# LoRaWAN.net
KiCad netlist of a schematic drawn in Altium Designer
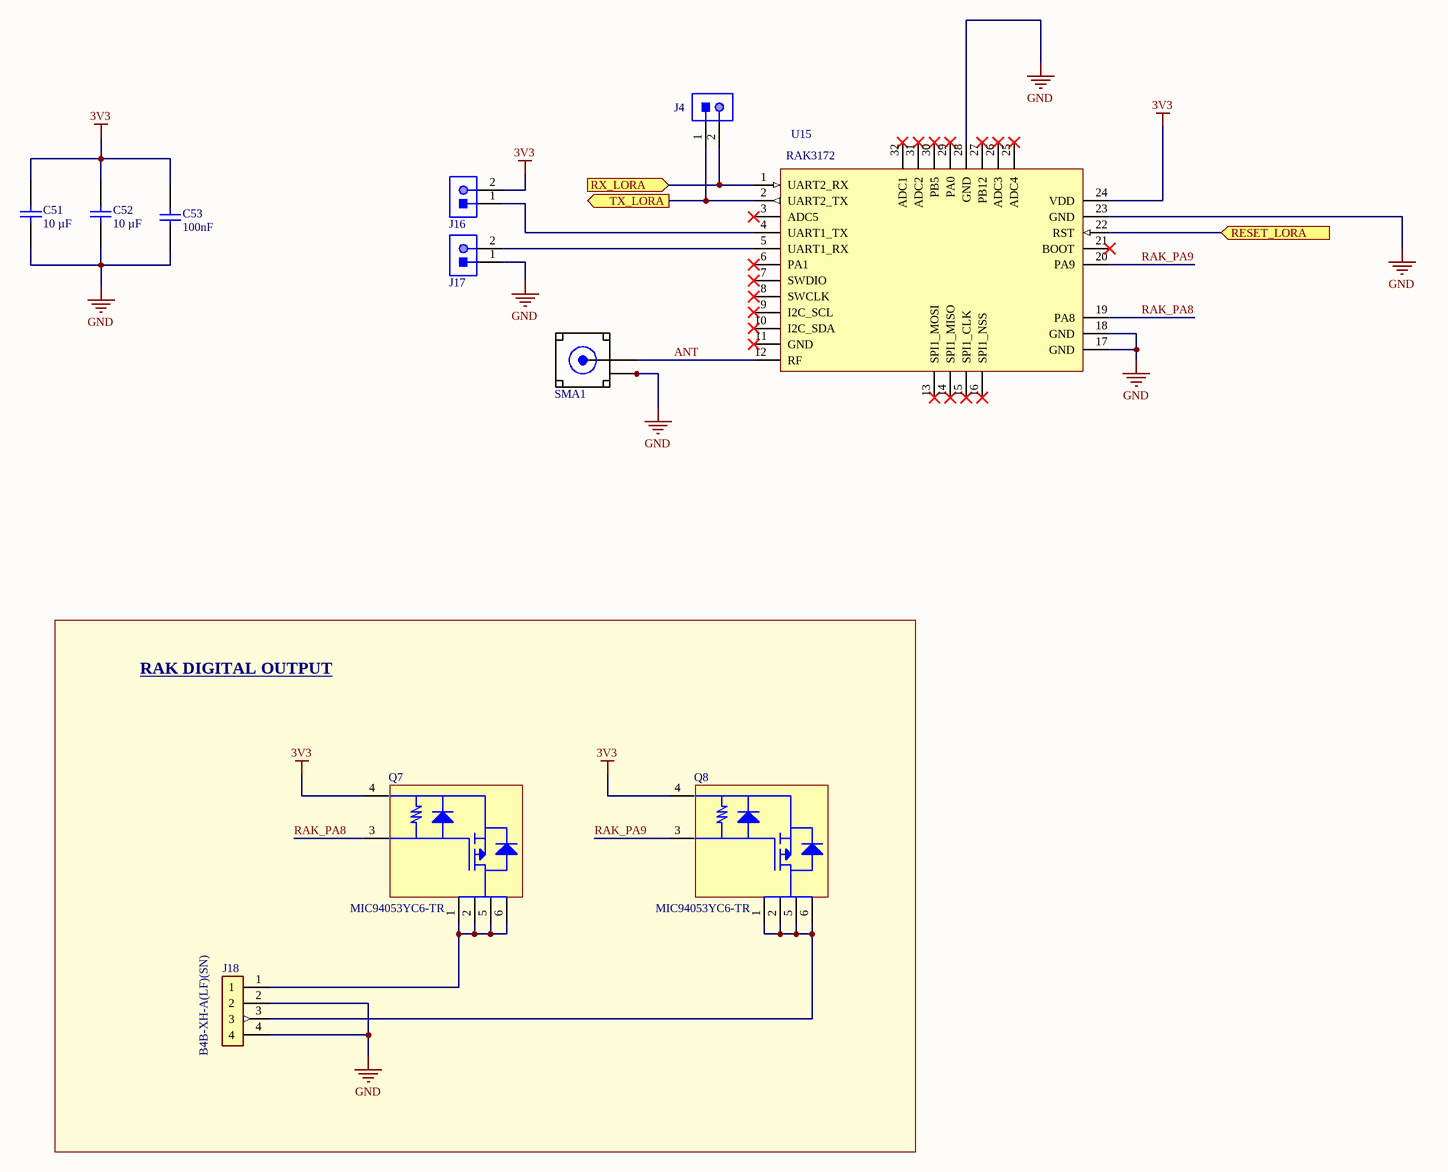
[diagram p0: LoRaWAN.SchDoc]

(export (version "E")
  (design (tool "Eeschema 10.0.6"))
  (components
    (comp (ref "C51")
      (value "10 µF")
      (footprint "Cap 0805 (2012 Metric)")
      (description "10 µF ±10% 10V Ceramic Capacitor X5R 0805 (2012 Metric)")
      (fields
        (field (name "MANUFACTURER") "Cal-Chip Electronics")
        (field (name "MANUFACTURER PART NUMBER") "GMC21X5R106K10NT")
      )
      (libsource (lib "Daniel_Integrated_Library") (part "Capacitor"))
    )
    (comp (ref "C52")
      (value "10 µF")
      (footprint "Cap 0805 (2012 Metric)")
      (description "10 µF ±10% 10V Ceramic Capacitor X5R 0805 (2012 Metric)")
      (fields
        (field (name "MANUFACTURER") "Cal-Chip Electronics")
        (field (name "MANUFACTURER PART NUMBER") "GMC21X5R106K10NT")
      )
      (libsource (lib "Daniel_Integrated_Library") (part "Capacitor"))
    )
    (comp (ref "C53")
      (value "100nF")
      (footprint "Cap 0805 (2012 Metric)")
      (description "Cap Ceramic 0.1uF 50V X7R 10% Pad SMD 0805 125C Automotive T/R")
      (fields
        (field (name "MANUFACTURER") "Samsung")
        (field (name "MANUFACTURER PART NUMBER") "CL21B104KBC5PNL")
      )
      (libsource (lib "Daniel_Integrated_Library") (part "Capacitor"))
    )
    (comp (ref "J4")
      (value "Header 2x1")
      (footprint "Header 2x1")
      (libsource (lib "Daniel_Integrated_Library") (part "Header 2x1"))
    )
    (comp (ref "J16")
      (value "Header 2x1")
      (footprint "Header 2x1")
      (libsource (lib "") (part "Header 2x1_1"))
    )
    (comp (ref "J17")
      (value "Header 2x1")
      (footprint "Header 2x1")
      (libsource (lib "") (part "Header 2x1_1"))
    )
    (comp (ref "J18")
      (value "B4B-XH-A(LF)(SN)")
      (footprint "B4B-XH-A(LF)(SN)")
      (fields (field (name "MANUFACTURER") "JST"))
      (libsource (lib "stratos") (part "B4B-XH-A(LF)(SN)"))
    )
    (comp (ref "Q7")
      (value "MIC94053YC6-TR")
      (footprint "SC-70-6")
      (description "P-Channel 6V 2A (Ta) 270mW (Ta) Surface Mount SC-70-6")
      (fields (field (name "MANUFACTURER") "Microchip"))
      (libsource (lib "Daniel_Integrated_Library") (part "TransistorMosfet(Load)"))
    )
    (comp (ref "Q8")
      (value "MIC94053YC6-TR")
      (footprint "SC-70-6")
      (description "P-Channel 6V 2A (Ta) 270mW (Ta) Surface Mount SC-70-6")
      (fields (field (name "MANUFACTURER") "Microchip"))
      (libsource (lib "Daniel_Integrated_Library") (part "TransistorMosfet(Load)"))
    )
    (comp (ref "SMA1")
      (value "https://www.digikey.com/products/en?keywords=5-1814400-1")
      (footprint "5-1814400-1+ant")
      (description "CONN SMA JACK R/A 50 OHM PCB")
      (fields
        (field (name "MANUFACTURER") "AMP - TE CONNECTIVITY")
        (field (name "MANUFACTURER PART NUMBER") "5-1814400-1")
      )
      (libsource (lib "MyLib") (part "5-1814400-1"))
    )
    (comp (ref "U15")
      (value "RAK3172")
      (footprint "RAK3172")
      (description "RAK3172 WisDuo LPWAN Module")
      (fields (field (name "MANUFACTURER") "RAK"))
      (libsource (lib "stratos") (part "RAK3172"))
    )
  )
  (nets
    (net (code "2") (name "/ANT") (class "Default")
      (node (ref "SMA1") (pin "5") (pinfunction "SIGNAL_5") (pintype "passive"))
      (node (ref "U15") (pin "12") (pinfunction "RF_12") (pintype "passive"))
    )
    (net (code "3") (name "/RAK_PA8") (class "Default")
      (node (ref "Q7") (pin "3") (pinfunction "G_3") (pintype "passive"))
      (node (ref "U15") (pin "19") (pinfunction "PA8_19") (pintype "passive"))
    )
    (net (code "4") (name "/RAK_PA9") (class "Default")
      (node (ref "Q8") (pin "3") (pinfunction "G_3") (pintype "passive"))
      (node (ref "U15") (pin "20") (pinfunction "PA9_20") (pintype "passive"))
    )
    (net (code "5") (name "/RESET_LORA") (class "Default")
      (node (ref "U15") (pin "22") (pinfunction "RST_22") (pintype "input"))
    )
    (net (code "6") (name "/RX_LORA") (class "Default")
      (node (ref "J4") (pin "2") (pinfunction "2_2") (pintype "passive"))
      (node (ref "U15") (pin "1") (pinfunction "UART2_RX_1") (pintype "input"))
    )
    (net (code "7") (name "/TX_LORA") (class "Default")
      (node (ref "J4") (pin "1") (pinfunction "1_1") (pintype "passive"))
      (node (ref "U15") (pin "2") (pinfunction "UART2_TX_2") (pintype "output"))
    )
    (net (code "8") (name "3V3") (class "Default")
      (node (ref "C51") (pin "1") (pinfunction "1_1") (pintype "passive"))
      (node (ref "C52") (pin "1") (pinfunction "1_1") (pintype "passive"))
      (node (ref "C53") (pin "1") (pinfunction "1_1") (pintype "passive"))
      (node (ref "J16") (pin "2") (pinfunction "2_2") (pintype "passive"))
      (node (ref "Q7") (pin "4") (pinfunction "S_4") (pintype "passive"))
      (node (ref "Q8") (pin "4") (pinfunction "S_4") (pintype "passive"))
      (node (ref "U15") (pin "24") (pinfunction "VDD_24") (pintype "passive"))
    )
    (net (code "9") (name "GND") (class "Default")
      (node (ref "C51") (pin "2") (pinfunction "2_2") (pintype "passive"))
      (node (ref "C52") (pin "2") (pinfunction "2_2") (pintype "passive"))
      (node (ref "C53") (pin "2") (pinfunction "2_2") (pintype "passive"))
      (node (ref "J17") (pin "1") (pinfunction "1_1") (pintype "passive"))
      (node (ref "J18") (pin "2") (pinfunction "2_2") (pintype "passive"))
      (node (ref "J18") (pin "4") (pinfunction "4_4") (pintype "passive"))
      (node (ref "SMA1") (pin "1") (pinfunction "GND_1") (pintype "power_in"))
      (node (ref "SMA1") (pin "2") (pinfunction "GND_2") (pintype "power_in"))
      (node (ref "SMA1") (pin "3") (pinfunction "GND_3") (pintype "power_in"))
      (node (ref "SMA1") (pin "4") (pinfunction "GND_4") (pintype "power_in"))
      (node (ref "U15") (pin "17") (pinfunction "GND_17") (pintype "passive"))
      (node (ref "U15") (pin "18") (pinfunction "GND_18") (pintype "passive"))
      (node (ref "U15") (pin "23") (pinfunction "GND_23") (pintype "passive"))
      (node (ref "U15") (pin "28") (pinfunction "GND_28") (pintype "passive"))
    )
    (net (code "10") (name "Net-(J18-Pad1)") (class "Default")
      (node (ref "J18") (pin "1") (pinfunction "1_1") (pintype "passive"))
      (node (ref "Q7") (pin "1") (pinfunction "D_1") (pintype "passive"))
      (node (ref "Q7") (pin "2") (pinfunction "D_2") (pintype "passive"))
      (node (ref "Q7") (pin "5") (pinfunction "D_5") (pintype "passive"))
      (node (ref "Q7") (pin "6") (pinfunction "D_6") (pintype "passive"))
    )
    (net (code "11") (name "Net-(J18-Pad3)") (class "Default")
      (node (ref "J18") (pin "3") (pinfunction "3_3") (pintype "output"))
      (node (ref "Q8") (pin "1") (pinfunction "D_1") (pintype "passive"))
      (node (ref "Q8") (pin "2") (pinfunction "D_2") (pintype "passive"))
      (node (ref "Q8") (pin "5") (pinfunction "D_5") (pintype "passive"))
      (node (ref "Q8") (pin "6") (pinfunction "D_6") (pintype "passive"))
    )
    (net (code "12") (name "Net-(U15-UART1_RX)") (class "Default")
      (node (ref "J17") (pin "2") (pinfunction "2_2") (pintype "passive"))
      (node (ref "U15") (pin "5") (pinfunction "UART1_RX_5") (pintype "passive"))
    )
    (net (code "13") (name "Net-(U15-UART1_TX)") (class "Default")
      (node (ref "J16") (pin "1") (pinfunction "1_1") (pintype "passive"))
      (node (ref "U15") (pin "4") (pinfunction "UART1_TX_4") (pintype "passive"))
    )
    (net (code "14") (name "unconnected-(U15-ADC1-Pad32)") (class "Default")
      (node (ref "U15") (pin "32") (pinfunction "ADC1_32") (pintype "passive+no_connect"))
    )
    (net (code "15") (name "unconnected-(U15-ADC2-Pad31)") (class "Default")
      (node (ref "U15") (pin "31") (pinfunction "ADC2_31") (pintype "passive+no_connect"))
    )
    (net (code "16") (name "unconnected-(U15-ADC3-Pad26)") (class "Default")
      (node (ref "U15") (pin "26") (pinfunction "ADC3_26") (pintype "passive+no_connect"))
    )
    (net (code "17") (name "unconnected-(U15-ADC4-Pad25)") (class "Default")
      (node (ref "U15") (pin "25") (pinfunction "ADC4_25") (pintype "passive+no_connect"))
    )
    (net (code "18") (name "unconnected-(U15-ADC5-Pad3)") (class "Default")
      (node (ref "U15") (pin "3") (pinfunction "ADC5_3") (pintype "passive+no_connect"))
    )
    (net (code "19") (name "unconnected-(U15-BOOT-Pad21)") (class "Default")
      (node (ref "U15") (pin "21") (pinfunction "BOOT_21") (pintype "passive+no_connect"))
    )
    (net (code "20") (name "unconnected-(U15-GND-Pad11)") (class "Default")
      (node (ref "U15") (pin "11") (pinfunction "GND_11") (pintype "passive+no_connect"))
    )
    (net (code "21") (name "unconnected-(U15-I2C_SCL-Pad9)") (class "Default")
      (node (ref "U15") (pin "9") (pinfunction "I2C_SCL_9") (pintype "passive+no_connect"))
    )
    (net (code "22") (name "unconnected-(U15-I2C_SDA-Pad10)") (class "Default")
      (node (ref "U15") (pin "10") (pinfunction "I2C_SDA_10") (pintype "passive+no_connect"))
    )
    (net (code "23") (name "unconnected-(U15-PA0-Pad29)") (class "Default")
      (node (ref "U15") (pin "29") (pinfunction "PA0_29") (pintype "passive+no_connect"))
    )
    (net (code "24") (name "unconnected-(U15-PA1-Pad6)") (class "Default")
      (node (ref "U15") (pin "6") (pinfunction "PA1_6") (pintype "passive+no_connect"))
    )
    (net (code "25") (name "unconnected-(U15-PB5-Pad30)") (class "Default")
      (node (ref "U15") (pin "30") (pinfunction "PB5_30") (pintype "passive+no_connect"))
    )
    (net (code "26") (name "unconnected-(U15-PB12-Pad27)") (class "Default")
      (node (ref "U15") (pin "27") (pinfunction "PB12_27") (pintype "passive+no_connect"))
    )
    (net (code "27") (name "unconnected-(U15-SPI1_CLK-Pad15)") (class "Default")
      (node (ref "U15") (pin "15") (pinfunction "SPI1_CLK_15") (pintype "passive+no_connect"))
    )
    (net (code "28") (name "unconnected-(U15-SPI1_MISO-Pad14)") (class "Default")
      (node (ref "U15") (pin "14") (pinfunction "SPI1_MISO_14") (pintype "passive+no_connect"))
    )
    (net (code "29") (name "unconnected-(U15-SPI1_MOSI-Pad13)") (class "Default")
      (node (ref "U15") (pin "13") (pinfunction "SPI1_MOSI_13") (pintype "passive+no_connect"))
    )
    (net (code "30") (name "unconnected-(U15-SPI1_NSS-Pad16)") (class "Default")
      (node (ref "U15") (pin "16") (pinfunction "SPI1_NSS_16") (pintype "passive+no_connect"))
    )
    (net (code "31") (name "unconnected-(U15-SWCLK-Pad8)") (class "Default")
      (node (ref "U15") (pin "8") (pinfunction "SWCLK_8") (pintype "passive+no_connect"))
    )
    (net (code "32") (name "unconnected-(U15-SWDIO-Pad7)") (class "Default")
      (node (ref "U15") (pin "7") (pinfunction "SWDIO_7") (pintype "passive+no_connect"))
    )
  )
)
